# Thermistor.net
KiCad netlist of a schematic drawn in EAGLE
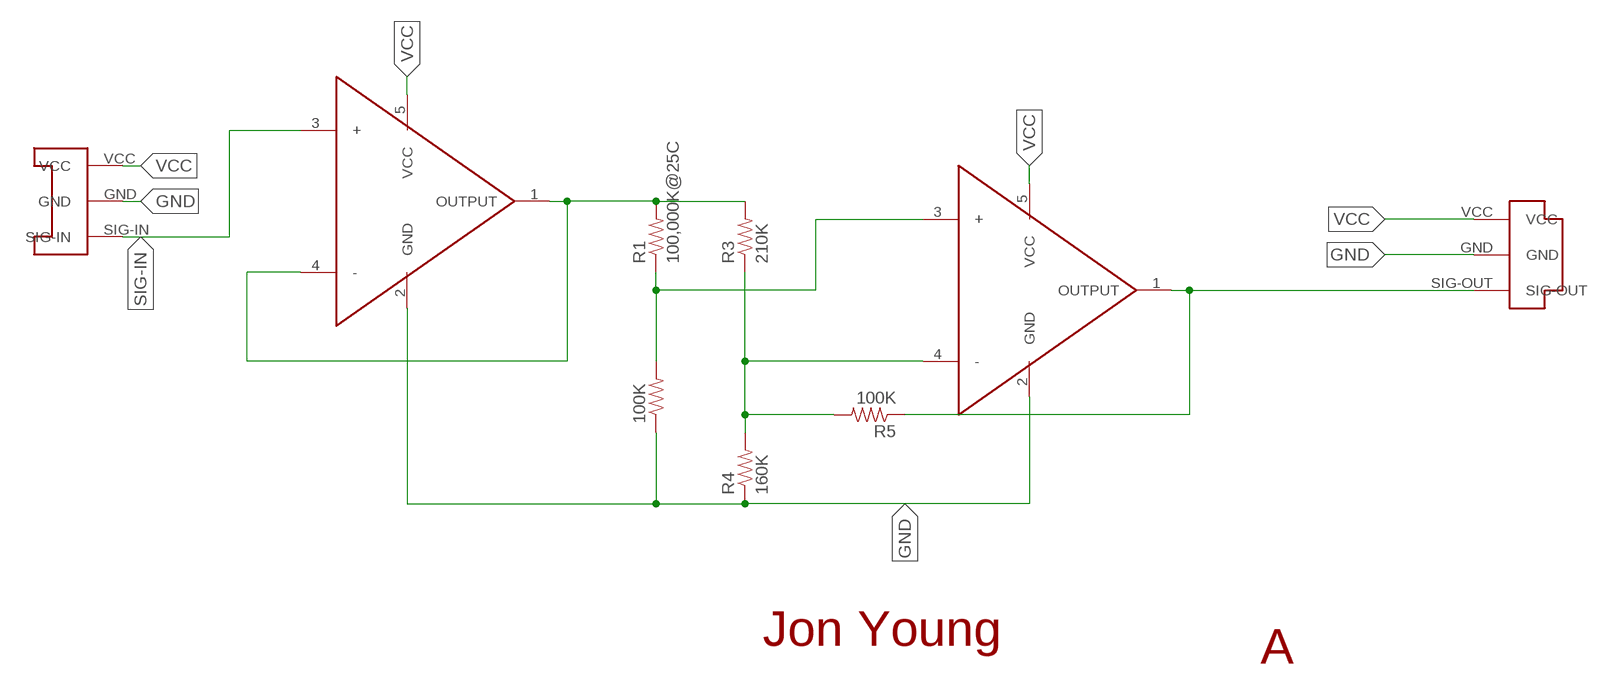
[diagram p0: schematic, sheet 1]

(export (version "E")
  (design (tool "Eeschema 10.0.6"))
  (components
    (comp (ref "100K")
      (value "RESISTOR0603")
      (footprint "eagle-import:0603-RES")
      (libsource (lib "eagle-import") (part "RESISTOR0603"))
    )
    (comp (ref "R1")
      (value "100,000K@25C")
      (footprint "eagle-import:0603-RES")
      (libsource (lib "eagle-import") (part "RESISTOR0603"))
    )
    (comp (ref "R3")
      (value "210K")
      (footprint "eagle-import:0603-RES")
      (libsource (lib "eagle-import") (part "RESISTOR0603"))
    )
    (comp (ref "R4")
      (value "160K")
      (footprint "eagle-import:0603-RES")
      (libsource (lib "eagle-import") (part "RESISTOR0603"))
    )
    (comp (ref "R5")
      (value "100K")
      (footprint "eagle-import:0603-RES")
      (libsource (lib "eagle-import") (part "RESISTOR0603"))
    )
    (comp (ref "U$1")
      (value "CONN-PLUG-3POS-3MM")
      (footprint "eagle-import:PLUG-3POS-3MM-SMD")
      (libsource (lib "eagle-import") (part "CONN-PLUG-3POS-3MM"))
    )
    (comp (ref "U$2")
      (value "CONN-SOCKET-3POS-3MM")
      (footprint "eagle-import:SOCKET-3POS-3MM-SMD")
      (libsource (lib "eagle-import") (part "CONN-SOCKET-3POS-3MM"))
    )
    (comp (ref "U$3")
      (value "OPAMP-MCP6001SOT23-5")
      (footprint "eagle-import:SOT23-5")
      (libsource (lib "eagle-import") (part "OPAMP-MCP6001SOT23-5"))
    )
    (comp (ref "U$4")
      (value "OPAMP-MCP6001SOT23-5")
      (footprint "eagle-import:SOT23-5")
      (libsource (lib "eagle-import") (part "OPAMP-MCP6001SOT23-5"))
    )
  )
  (nets
    (net (code "1") (name "GND") (class "Default")
      (node (ref "100K") (pin "1") (pinfunction "1_1") (pintype "passive"))
      (node (ref "R4") (pin "1") (pinfunction "1_1") (pintype "passive"))
      (node (ref "U$1") (pin "GND") (pinfunction "GND_GND") (pintype "power_in"))
      (node (ref "U$2") (pin "GND") (pinfunction "GND_GND") (pintype "power_in"))
      (node (ref "U$3") (pin "2") (pinfunction "GND_2") (pintype "power_in"))
      (node (ref "U$4") (pin "2") (pinfunction "GND_2") (pintype "power_in"))
    )
    (net (code "2") (name "Net-(U$3--)") (class "Default")
      (node (ref "R1") (pin "2") (pinfunction "2_2") (pintype "passive"))
      (node (ref "R3") (pin "2") (pinfunction "2_2") (pintype "passive"))
      (node (ref "U$3") (pin "1") (pinfunction "OUTPUT_1") (pintype "output"))
      (node (ref "U$3") (pin "4") (pinfunction "-_4") (pintype "input"))
    )
    (net (code "3") (name "Net-(U$4-+)") (class "Default")
      (node (ref "100K") (pin "2") (pinfunction "2_2") (pintype "passive"))
      (node (ref "R1") (pin "1") (pinfunction "1_1") (pintype "passive"))
      (node (ref "U$4") (pin "3") (pinfunction "+_3") (pintype "input"))
    )
    (net (code "4") (name "Net-(U$4--)") (class "Default")
      (node (ref "R3") (pin "1") (pinfunction "1_1") (pintype "passive"))
      (node (ref "R4") (pin "2") (pinfunction "2_2") (pintype "passive"))
      (node (ref "R5") (pin "2") (pinfunction "2_2") (pintype "passive"))
      (node (ref "U$4") (pin "4") (pinfunction "-_4") (pintype "input"))
    )
    (net (code "5") (name "Net-(U$4-OUTPUT)") (class "Default")
      (node (ref "R5") (pin "1") (pinfunction "1_1") (pintype "passive"))
      (node (ref "U$1") (pin "SIG-OUT") (pinfunction "SIG-OUT_SIG-OUT") (pintype "bidirectional"))
      (node (ref "U$4") (pin "1") (pinfunction "OUTPUT_1") (pintype "output"))
    )
    (net (code "6") (name "SIG-IN") (class "Default")
      (node (ref "U$2") (pin "SIG-IN") (pinfunction "SIG-IN_SIG-IN") (pintype "bidirectional"))
      (node (ref "U$3") (pin "3") (pinfunction "+_3") (pintype "input"))
    )
    (net (code "7") (name "VCC") (class "Default")
      (node (ref "U$1") (pin "VCC") (pinfunction "VCC_VCC") (pintype "power_in"))
      (node (ref "U$2") (pin "VCC") (pinfunction "VCC_VCC") (pintype "power_in"))
      (node (ref "U$3") (pin "5") (pinfunction "VCC_5") (pintype "power_in"))
      (node (ref "U$4") (pin "5") (pinfunction "VCC_5") (pintype "power_in"))
    )
  )
)
